# LED_Driver_-_1.net
KiCad netlist of a schematic drawn in Altium Designer
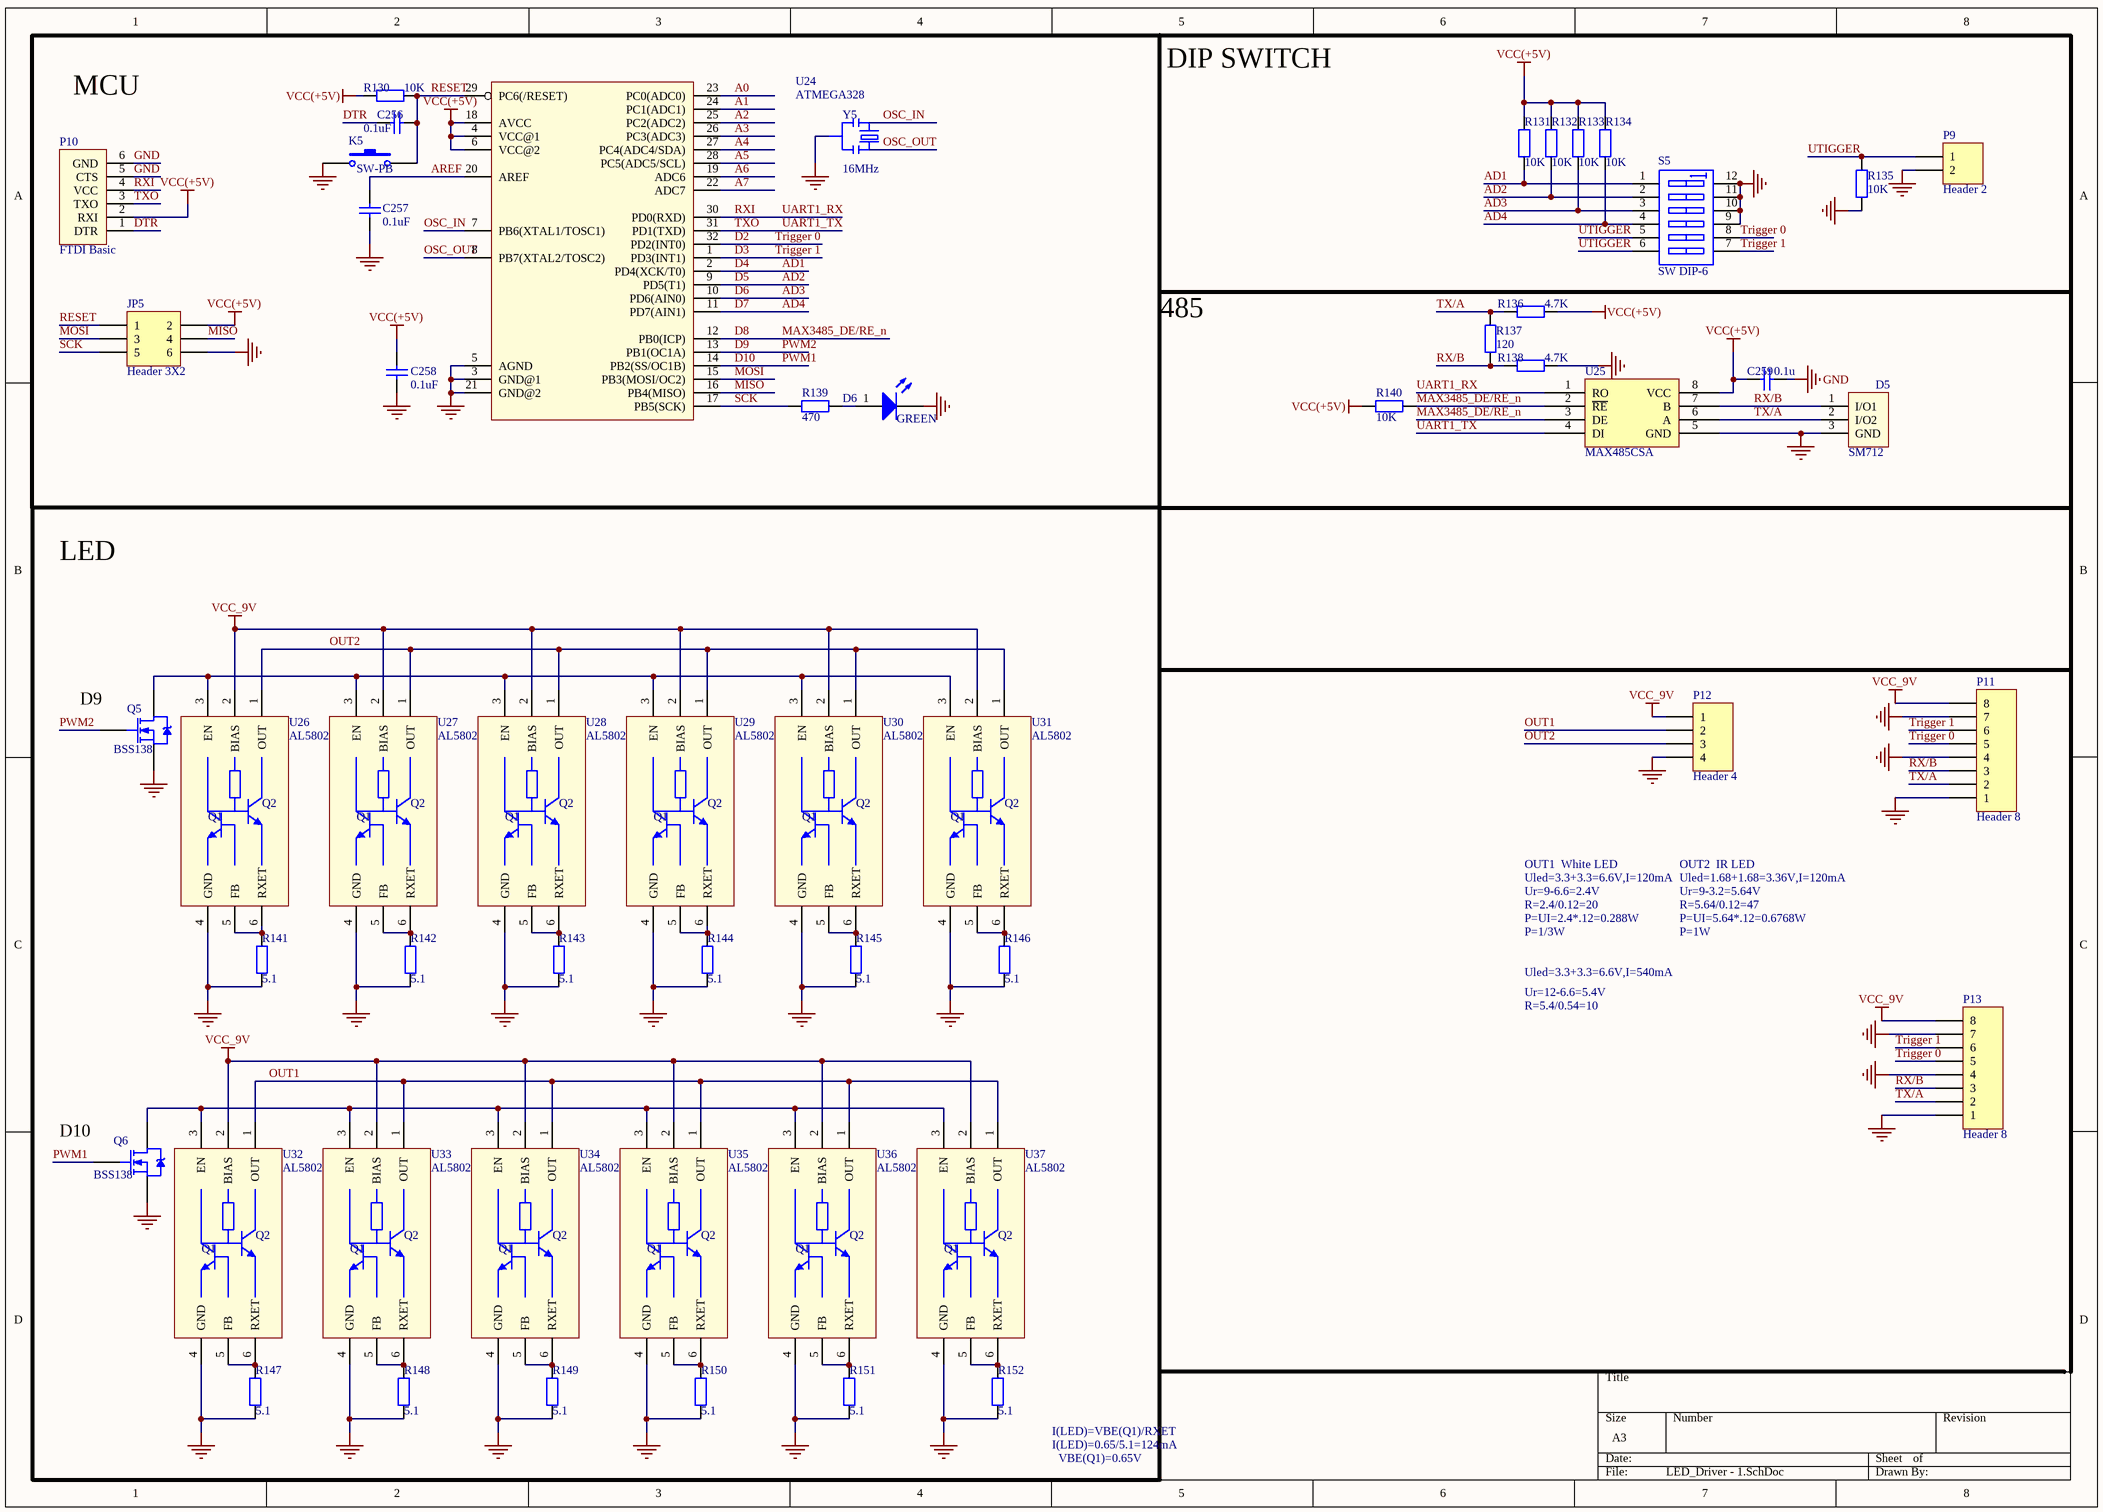
[diagram p0: LED_Driver - 1.SchDoc]

(export (version "E")
  (design (tool "Eeschema 10.0.6"))
  (components
    (comp (ref "C256")
      (value "0.1uF")
      (footprint "C0603")
      (description "Capacitor")
      (fields (field (name "IPARTNUMBER") "C100nF25V10%X7R") (field (name "VOLTAGE") "25V"))
      (libsource (lib "Schlib1") (part "CAP SMT C100nF25V10%X7R"))
    )
    (comp (ref "C257")
      (value "0.1uF")
      (footprint "C0603")
      (description "Capacitor")
      (fields (field (name "IPARTNUMBER") "C100nF25V10%X7R") (field (name "VOLTAGE") "25V"))
      (libsource (lib "Schlib1") (part "CAP SMT C100nF25V10%X7R"))
    )
    (comp (ref "C258")
      (value "0.1uF")
      (footprint "C0603")
      (description "Capacitor")
      (fields (field (name "IPARTNUMBER") "C100nF25V10%X7R") (field (name "VOLTAGE") "25V"))
      (libsource (lib "Schlib1") (part "CAP SMT C100nF25V10%X7R"))
    )
    (comp (ref "C259")
      (value "0.1u")
      (footprint "C0603")
      (description "Capacitor")
      (fields (field (name "PUBLISHER") "Altium Limited"))
      (libsource (lib "Miscellaneous Devices") (part "Cap"))
    )
    (comp (ref "D5")
      (value "SM712")
      (footprint "SOT23-3")
      (libsource (lib "STM32F4_CAM V2.0") (part "SM712"))
    )
    (comp (ref "D6")
      (value "GREEN")
      (footprint "LED0805")
      (description "Typical INFRARED GaAs LED")
      (fields (field (name "PUBLISHER") "Altium Limited"))
      (libsource (lib "DM642") (part "LED0"))
    )
    (comp (ref "JP5")
      (value "Header 3X2")
      (footprint "MHDR1X6")
      (description "Header, 3-Pin, Dual row")
      (fields (field (name "PUBLISHER") "Altium Limited"))
      (libsource (lib "Miscellaneous Connectors") (part "Header 3X2"))
    )
    (comp (ref "K5")
      (value "SW-PB")
      (footprint "157SW")
      (description "Switch")
      (fields (field (name "PUBLISHER") "Altium Limited"))
      (libsource (lib "Miscellaneous Devices") (part "SW-PB"))
    )
    (comp (ref "P9")
      (value "Header 2")
      (footprint "HDR1X2")
      (description "Header, 2-Pin")
      (fields (field (name "PUBLISHER") "Altium Limited"))
      (libsource (lib "Miscellaneous Connectors") (part "Header 2"))
    )
    (comp (ref "P10")
      (value "FTDI Basic")
      (footprint "MHDR1X6")
      (libsource (lib "PCB_Project1") (part "ARDUINO_SERIAL_PROGRAMPTH"))
    )
    (comp (ref "P11")
      (value "Header 8")
      (footprint "SH_1.25MM*8")
      (description "Header, 8-Pin")
      (fields (field (name "PUBLISHER") "Altium Limited"))
      (libsource (lib "Miscellaneous Connectors") (part "Header 8"))
    )
    (comp (ref "P12")
      (value "Header 4")
      (footprint "SMT_1.25MM*4")
      (description "Header, 4-Pin")
      (fields (field (name "PUBLISHER") "Altium Limited"))
      (libsource (lib "Miscellaneous Connectors") (part "Header 4"))
    )
    (comp (ref "P13")
      (value "Header 8")
      (footprint "SH_1.25MM*8")
      (description "Header, 8-Pin")
      (fields (field (name "PUBLISHER") "Altium Limited"))
      (libsource (lib "Miscellaneous Connectors") (part "Header 8"))
    )
    (comp (ref "Q5")
      (value "BSS138")
      (footprint "SOT-23 (Standard)")
      (fields
        (field (name "MANUFACTURER") "Fairchild Semiconductor")
        (field (name "MANUFACTURER PART NUMBER") "BSS123")
      )
      (libsource (lib "Miscellaneous_Devices") (part "NMOS"))
    )
    (comp (ref "Q6")
      (value "BSS138")
      (footprint "SOT-23 (Standard)")
      (fields
        (field (name "MANUFACTURER") "Fairchild Semiconductor")
        (field (name "MANUFACTURER PART NUMBER") "BSS123")
      )
      (libsource (lib "Miscellaneous_Devices") (part "NMOS"))
    )
    (comp (ref "R130")
      (value "10K")
      (footprint "R0603")
      (description "Resistor")
      (libsource (lib "") (part "Res2_2"))
    )
    (comp (ref "R131")
      (value "10K")
      (footprint "R0603")
      (description "Resistor")
      (libsource (lib "") (part "Res2_1"))
    )
    (comp (ref "R132")
      (value "10K")
      (footprint "R0603")
      (description "Resistor")
      (libsource (lib "") (part "Res2_1"))
    )
    (comp (ref "R133")
      (value "10K")
      (footprint "R0603")
      (description "Resistor")
      (libsource (lib "") (part "Res2_1"))
    )
    (comp (ref "R134")
      (value "10K")
      (footprint "R0603")
      (description "Resistor")
      (libsource (lib "") (part "Res2_1"))
    )
    (comp (ref "R135")
      (value "10K")
      (footprint "R0603")
      (description "Resistor")
      (fields (field (name "PUBLISHER") "Altium Limited"))
      (libsource (lib "Miscellaneous Devices") (part "Res2"))
    )
    (comp (ref "R136")
      (value "4.7K")
      (footprint "R0603")
      (description "Resistor")
      (libsource (lib "DM642") (part "Res2"))
    )
    (comp (ref "R137")
      (value "120")
      (footprint "R0603")
      (description "Resistor")
      (libsource (lib "") (part "Res2_1"))
    )
    (comp (ref "R138")
      (value "4.7K")
      (footprint "R0603")
      (description "Resistor")
      (libsource (lib "DM642") (part "Res2"))
    )
    (comp (ref "R139")
      (value "470")
      (footprint "R0603")
      (description "Resistor")
      (libsource (lib "") (part "Res2_2"))
    )
    (comp (ref "R140")
      (value "10K")
      (footprint "R0603")
      (description "Resistor")
      (libsource (lib "DM642") (part "Res2"))
    )
    (comp (ref "R141")
      (value "5.1")
      (footprint "R0603")
      (description "Resistor")
      (libsource (lib "") (part "Res2_1"))
    )
    (comp (ref "R142")
      (value "5.1")
      (footprint "R0603")
      (description "Resistor")
      (libsource (lib "") (part "Res2_1"))
    )
    (comp (ref "R143")
      (value "5.1")
      (footprint "R0603")
      (description "Resistor")
      (libsource (lib "") (part "Res2_1"))
    )
    (comp (ref "R144")
      (value "5.1")
      (footprint "R0603")
      (description "Resistor")
      (libsource (lib "") (part "Res2_1"))
    )
    (comp (ref "R145")
      (value "5.1")
      (footprint "R0603")
      (description "Resistor")
      (libsource (lib "") (part "Res2_1"))
    )
    (comp (ref "R146")
      (value "5.1")
      (footprint "R0603")
      (description "Resistor")
      (libsource (lib "") (part "Res2_1"))
    )
    (comp (ref "R147")
      (value "5.1")
      (footprint "R0603")
      (description "Resistor")
      (libsource (lib "") (part "Res2_1"))
    )
    (comp (ref "R148")
      (value "5.1")
      (footprint "R0603")
      (description "Resistor")
      (libsource (lib "") (part "Res2_1"))
    )
    (comp (ref "R149")
      (value "5.1")
      (footprint "R0603")
      (description "Resistor")
      (libsource (lib "") (part "Res2_1"))
    )
    (comp (ref "R150")
      (value "5.1")
      (footprint "R0603")
      (description "Resistor")
      (libsource (lib "") (part "Res2_1"))
    )
    (comp (ref "R151")
      (value "5.1")
      (footprint "R0603")
      (description "Resistor")
      (libsource (lib "") (part "Res2_1"))
    )
    (comp (ref "R152")
      (value "5.1")
      (footprint "R0603")
      (description "Resistor")
      (libsource (lib "") (part "Res2_1"))
    )
    (comp (ref "S5")
      (value "SW DIP-6")
      (footprint "DIP_SW_6WAY_SMD")
      (description "DIP Switch, 6 Position, SPST")
      (fields (field (name "PUBLISHER") "Altium Limited"))
      (libsource (lib "Miscellaneous Devices") (part "SW DIP-6"))
    )
    (comp (ref "U24")
      (value "ATMEGA328")
      (footprint "TQFP32-08")
      (libsource (lib "PCB_Project1") (part "ATMEGA168"))
    )
    (comp (ref "U25")
      (value "MAX485CSA")
      (footprint "SOIC-8")
      (libsource (lib "STM32F4_CAM V1.2") (part "MAX3485CSA"))
    )
    (comp (ref "U26") (value "AL5802") (footprint "SOT26") (libsource (lib "LED") (part "AL5802")))
    (comp (ref "U27") (value "AL5802") (footprint "SOT26") (libsource (lib "LED") (part "AL5802")))
    (comp (ref "U28") (value "AL5802") (footprint "SOT26") (libsource (lib "LED") (part "AL5802")))
    (comp (ref "U29") (value "AL5802") (footprint "SOT26") (libsource (lib "LED") (part "AL5802")))
    (comp (ref "U30") (value "AL5802") (footprint "SOT26") (libsource (lib "LED") (part "AL5802")))
    (comp (ref "U31") (value "AL5802") (footprint "SOT26") (libsource (lib "LED") (part "AL5802")))
    (comp (ref "U32") (value "AL5802") (footprint "SOT26") (libsource (lib "LED") (part "AL5802")))
    (comp (ref "U33") (value "AL5802") (footprint "SOT26") (libsource (lib "LED") (part "AL5802")))
    (comp (ref "U34") (value "AL5802") (footprint "SOT26") (libsource (lib "LED") (part "AL5802")))
    (comp (ref "U35") (value "AL5802") (footprint "SOT26") (libsource (lib "LED") (part "AL5802")))
    (comp (ref "U36") (value "AL5802") (footprint "SOT26") (libsource (lib "LED") (part "AL5802")))
    (comp (ref "U37") (value "AL5802") (footprint "SOT26") (libsource (lib "LED") (part "AL5802")))
    (comp (ref "Y5")
      (value "16MHz")
      (footprint "RESONATOR-SMD")
      (libsource (lib "SparkFun") (part "RESONATORSMD"))
    )
  )
  (nets
    (net (code "1") (name "/A0") (class "Default")
      (node (ref "U24") (pin "23") (pinfunction "PC0(ADC0)_23") (pintype "passive"))
    )
    (net (code "2") (name "/A1") (class "Default")
      (node (ref "U24") (pin "24") (pinfunction "PC1(ADC1)_24") (pintype "passive"))
    )
    (net (code "3") (name "/A2") (class "Default")
      (node (ref "U24") (pin "25") (pinfunction "PC2(ADC2)_25") (pintype "passive"))
    )
    (net (code "4") (name "/A3") (class "Default")
      (node (ref "U24") (pin "26") (pinfunction "PC3(ADC3)_26") (pintype "passive"))
    )
    (net (code "5") (name "/A4") (class "Default")
      (node (ref "U24") (pin "27") (pinfunction "PC4(ADC4/SDA)_27") (pintype "passive"))
    )
    (net (code "6") (name "/A5") (class "Default")
      (node (ref "U24") (pin "28") (pinfunction "PC5(ADC5/SCL)_28") (pintype "passive"))
    )
    (net (code "7") (name "/A6") (class "Default")
      (node (ref "U24") (pin "19") (pinfunction "ADC6_19") (pintype "passive"))
    )
    (net (code "8") (name "/A7") (class "Default")
      (node (ref "U24") (pin "22") (pinfunction "ADC7_22") (pintype "passive"))
    )
    (net (code "9") (name "/AD1") (class "Default")
      (node (ref "R131") (pin "2") (pinfunction "2_2") (pintype "passive"))
      (node (ref "S5") (pin "1") (pinfunction "A1_1") (pintype "passive"))
      (node (ref "U24") (pin "2") (pinfunction "PD4(XCK/T0)_2") (pintype "passive"))
    )
    (net (code "10") (name "/AD2") (class "Default")
      (node (ref "R132") (pin "2") (pinfunction "2_2") (pintype "passive"))
      (node (ref "S5") (pin "2") (pinfunction "A2_2") (pintype "passive"))
      (node (ref "U24") (pin "9") (pinfunction "PD5(T1)_9") (pintype "passive"))
    )
    (net (code "11") (name "/AD3") (class "Default")
      (node (ref "R133") (pin "2") (pinfunction "2_2") (pintype "passive"))
      (node (ref "S5") (pin "3") (pinfunction "A3_3") (pintype "passive"))
      (node (ref "U24") (pin "10") (pinfunction "PD6(AIN0)_10") (pintype "passive"))
    )
    (net (code "12") (name "/AD4") (class "Default")
      (node (ref "R134") (pin "2") (pinfunction "2_2") (pintype "passive"))
      (node (ref "S5") (pin "4") (pinfunction "A4_4") (pintype "passive"))
      (node (ref "U24") (pin "11") (pinfunction "PD7(AIN1)_11") (pintype "passive"))
    )
    (net (code "13") (name "/AREF") (class "Default")
      (node (ref "C257") (pin "2") (pinfunction "2_2") (pintype "passive"))
      (node (ref "U24") (pin "20") (pinfunction "AREF_20") (pintype "passive"))
    )
    (net (code "14") (name "/D2") (class "Default")
      (node (ref "P11") (pin "5") (pinfunction "5_5") (pintype "passive"))
      (node (ref "P13") (pin "5") (pinfunction "5_5") (pintype "passive"))
      (node (ref "S5") (pin "8") (pinfunction "B5_8") (pintype "passive"))
      (node (ref "U24") (pin "32") (pinfunction "PD2(INT0)_32") (pintype "passive"))
    )
    (net (code "15") (name "/D3") (class "Default")
      (node (ref "P11") (pin "6") (pinfunction "6_6") (pintype "passive"))
      (node (ref "P13") (pin "6") (pinfunction "6_6") (pintype "passive"))
      (node (ref "S5") (pin "7") (pinfunction "B6_7") (pintype "passive"))
      (node (ref "U24") (pin "1") (pinfunction "PD3(INT1)_1") (pintype "passive"))
    )
    (net (code "16") (name "/D8") (class "Default")
      (node (ref "R140") (pin "1") (pinfunction "1_1") (pintype "passive"))
      (node (ref "U24") (pin "12") (pinfunction "PB0(ICP)_12") (pintype "passive"))
      (node (ref "U25") (pin "2") (pinfunction "~{RE}_2") (pintype "passive"))
      (node (ref "U25") (pin "3") (pinfunction "DE_3") (pintype "passive"))
    )
    (net (code "17") (name "/D9") (class "Default")
      (node (ref "Q5") (pin "G") (pinfunction "G_G") (pintype "passive"))
      (node (ref "U24") (pin "13") (pinfunction "PB1(OC1A)_13") (pintype "passive"))
    )
    (net (code "18") (name "/D10") (class "Default")
      (node (ref "Q6") (pin "G") (pinfunction "G_G") (pintype "passive"))
      (node (ref "U24") (pin "14") (pinfunction "PB2(SS/OC1B)_14") (pintype "passive"))
    )
    (net (code "19") (name "/DTR") (class "Default")
      (node (ref "C256") (pin "1") (pinfunction "1_1") (pintype "passive"))
      (node (ref "P10") (pin "1") (pinfunction "DTR_1") (pintype "passive"))
    )
    (net (code "20") (name "/MISO") (class "Default")
      (node (ref "JP5") (pin "4") (pinfunction "4_4") (pintype "passive"))
      (node (ref "U24") (pin "16") (pinfunction "PB4(MISO)_16") (pintype "passive"))
    )
    (net (code "21") (name "/MOSI") (class "Default")
      (node (ref "JP5") (pin "3") (pinfunction "3_3") (pintype "passive"))
      (node (ref "U24") (pin "15") (pinfunction "PB3(MOSI/OC2)_15") (pintype "passive"))
    )
    (net (code "22") (name "/OSC_IN") (class "Default")
      (node (ref "U24") (pin "7") (pinfunction "PB6(XTAL1/TOSC1)_7") (pintype "passive"))
      (node (ref "Y5") (pin "3") (pinfunction "3_3") (pintype "passive"))
    )
    (net (code "23") (name "/OSC_OUT") (class "Default")
      (node (ref "U24") (pin "8") (pinfunction "PB7(XTAL2/TOSC2)_8") (pintype "passive"))
      (node (ref "Y5") (pin "1") (pinfunction "1_1") (pintype "passive"))
    )
    (net (code "24") (name "/OUT1") (class "Default")
      (node (ref "P12") (pin "2") (pinfunction "2_2") (pintype "passive"))
      (node (ref "U32") (pin "1") (pinfunction "OUT_1") (pintype "passive"))
      (node (ref "U33") (pin "1") (pinfunction "OUT_1") (pintype "passive"))
      (node (ref "U34") (pin "1") (pinfunction "OUT_1") (pintype "passive"))
      (node (ref "U35") (pin "1") (pinfunction "OUT_1") (pintype "passive"))
      (node (ref "U36") (pin "1") (pinfunction "OUT_1") (pintype "passive"))
      (node (ref "U37") (pin "1") (pinfunction "OUT_1") (pintype "passive"))
    )
    (net (code "25") (name "/OUT2") (class "Default")
      (node (ref "P12") (pin "3") (pinfunction "3_3") (pintype "passive"))
      (node (ref "U26") (pin "1") (pinfunction "OUT_1") (pintype "passive"))
      (node (ref "U27") (pin "1") (pinfunction "OUT_1") (pintype "passive"))
      (node (ref "U28") (pin "1") (pinfunction "OUT_1") (pintype "passive"))
      (node (ref "U29") (pin "1") (pinfunction "OUT_1") (pintype "passive"))
      (node (ref "U30") (pin "1") (pinfunction "OUT_1") (pintype "passive"))
      (node (ref "U31") (pin "1") (pinfunction "OUT_1") (pintype "passive"))
    )
    (net (code "26") (name "/RESET") (class "Default")
      (node (ref "C256") (pin "2") (pinfunction "2_2") (pintype "passive"))
      (node (ref "JP5") (pin "1") (pinfunction "1_1") (pintype "passive"))
      (node (ref "K5") (pin "2") (pinfunction "2_2") (pintype "passive"))
      (node (ref "R130") (pin "2") (pinfunction "2_2") (pintype "passive"))
      (node (ref "U24") (pin "29") (pinfunction "PC6(/RESET)_29") (pintype "passive"))
    )
    (net (code "27") (name "/RXI") (class "Default")
      (node (ref "P10") (pin "4") (pinfunction "VCC_4") (pintype "passive"))
      (node (ref "U24") (pin "30") (pinfunction "PD0(RXD)_30") (pintype "passive"))
      (node (ref "U25") (pin "1") (pinfunction "RO_1") (pintype "passive"))
    )
    (net (code "28") (name "/RX{slash}B") (class "Default")
      (node (ref "D5") (pin "1") (pinfunction "I/O1_1") (pintype "passive"))
      (node (ref "P11") (pin "3") (pinfunction "3_3") (pintype "passive"))
      (node (ref "P13") (pin "3") (pinfunction "3_3") (pintype "passive"))
      (node (ref "R137") (pin "2") (pinfunction "2_2") (pintype "passive"))
      (node (ref "R138") (pin "2") (pinfunction "2_2") (pintype "passive"))
      (node (ref "U25") (pin "7") (pinfunction "B_7") (pintype "passive"))
    )
    (net (code "29") (name "/SCK") (class "Default")
      (node (ref "JP5") (pin "5") (pinfunction "5_5") (pintype "passive"))
      (node (ref "R139") (pin "1") (pinfunction "1_1") (pintype "passive"))
      (node (ref "U24") (pin "17") (pinfunction "PB5(SCK)_17") (pintype "passive"))
    )
    (net (code "30") (name "/TXO") (class "Default")
      (node (ref "P10") (pin "3") (pinfunction "TXO_3") (pintype "passive"))
      (node (ref "U24") (pin "31") (pinfunction "PD1(TXD)_31") (pintype "passive"))
      (node (ref "U25") (pin "4") (pinfunction "DI_4") (pintype "passive"))
    )
    (net (code "31") (name "/TX{slash}A") (class "Default")
      (node (ref "D5") (pin "2") (pinfunction "I/O2_2") (pintype "passive"))
      (node (ref "P11") (pin "2") (pinfunction "2_2") (pintype "passive"))
      (node (ref "P13") (pin "2") (pinfunction "2_2") (pintype "passive"))
      (node (ref "R136") (pin "2") (pinfunction "2_2") (pintype "passive"))
      (node (ref "R137") (pin "1") (pinfunction "1_1") (pintype "passive"))
      (node (ref "U25") (pin "6") (pinfunction "A_6") (pintype "passive"))
    )
    (net (code "32") (name "/UTIGGER") (class "Default")
      (node (ref "P9") (pin "1") (pinfunction "1_1") (pintype "passive"))
      (node (ref "R135") (pin "2") (pinfunction "2_2") (pintype "passive"))
      (node (ref "S5") (pin "5") (pinfunction "A5_5") (pintype "passive"))
      (node (ref "S5") (pin "6") (pinfunction "A6_6") (pintype "passive"))
    )
    (net (code "33") (name "GND") (class "Default")
      (node (ref "C257") (pin "1") (pinfunction "1_1") (pintype "passive"))
      (node (ref "C258") (pin "2") (pinfunction "2_2") (pintype "passive"))
      (node (ref "C259") (pin "1") (pinfunction "1_1") (pintype "passive"))
      (node (ref "D5") (pin "3") (pinfunction "GND_3") (pintype "passive"))
      (node (ref "D6") (pin "2") (pinfunction "K_2") (pintype "passive"))
      (node (ref "JP5") (pin "6") (pinfunction "6_6") (pintype "passive"))
      (node (ref "K5") (pin "1") (pinfunction "1_1") (pintype "passive"))
      (node (ref "P10") (pin "5") (pinfunction "CTS_5") (pintype "passive"))
      (node (ref "P10") (pin "6") (pinfunction "GND_6") (pintype "passive"))
      (node (ref "P11") (pin "1") (pinfunction "1_1") (pintype "passive"))
      (node (ref "P11") (pin "4") (pinfunction "4_4") (pintype "passive"))
      (node (ref "P11") (pin "7") (pinfunction "7_7") (pintype "passive"))
      (node (ref "P12") (pin "4") (pinfunction "4_4") (pintype "passive"))
      (node (ref "P13") (pin "1") (pinfunction "1_1") (pintype "passive"))
      (node (ref "P13") (pin "4") (pinfunction "4_4") (pintype "passive"))
      (node (ref "P13") (pin "7") (pinfunction "7_7") (pintype "passive"))
      (node (ref "P9") (pin "2") (pinfunction "2_2") (pintype "passive"))
      (node (ref "Q5") (pin "S") (pinfunction "S_S") (pintype "passive"))
      (node (ref "Q6") (pin "S") (pinfunction "S_S") (pintype "passive"))
      (node (ref "R135") (pin "1") (pinfunction "1_1") (pintype "passive"))
      (node (ref "R138") (pin "1") (pinfunction "1_1") (pintype "passive"))
      (node (ref "R141") (pin "2") (pinfunction "2_2") (pintype "passive"))
      (node (ref "R142") (pin "2") (pinfunction "2_2") (pintype "passive"))
      (node (ref "R143") (pin "2") (pinfunction "2_2") (pintype "passive"))
      (node (ref "R144") (pin "2") (pinfunction "2_2") (pintype "passive"))
      (node (ref "R145") (pin "2") (pinfunction "2_2") (pintype "passive"))
      (node (ref "R146") (pin "2") (pinfunction "2_2") (pintype "passive"))
      (node (ref "R147") (pin "2") (pinfunction "2_2") (pintype "passive"))
      (node (ref "R148") (pin "2") (pinfunction "2_2") (pintype "passive"))
      (node (ref "R149") (pin "2") (pinfunction "2_2") (pintype "passive"))
      (node (ref "R150") (pin "2") (pinfunction "2_2") (pintype "passive"))
      (node (ref "R151") (pin "2") (pinfunction "2_2") (pintype "passive"))
      (node (ref "R152") (pin "2") (pinfunction "2_2") (pintype "passive"))
      (node (ref "S5") (pin "10") (pinfunction "B3_10") (pintype "passive"))
      (node (ref "S5") (pin "11") (pinfunction "B2_11") (pintype "passive"))
      (node (ref "S5") (pin "12") (pinfunction "B1_12") (pintype "passive"))
      (node (ref "S5") (pin "9") (pinfunction "B4_9") (pintype "passive"))
      (node (ref "U24") (pin "21") (pinfunction "GND@2_21") (pintype "passive"))
      (node (ref "U24") (pin "3") (pinfunction "GND@1_3") (pintype "passive"))
      (node (ref "U24") (pin "5") (pinfunction "AGND_5") (pintype "passive"))
      (node (ref "U25") (pin "5") (pinfunction "GND_5") (pintype "passive"))
      (node (ref "U26") (pin "4") (pinfunction "GND_4") (pintype "passive"))
      (node (ref "U27") (pin "4") (pinfunction "GND_4") (pintype "passive"))
      (node (ref "U28") (pin "4") (pinfunction "GND_4") (pintype "passive"))
      (node (ref "U29") (pin "4") (pinfunction "GND_4") (pintype "passive"))
      (node (ref "U30") (pin "4") (pinfunction "GND_4") (pintype "passive"))
      (node (ref "U31") (pin "4") (pinfunction "GND_4") (pintype "passive"))
      (node (ref "U32") (pin "4") (pinfunction "GND_4") (pintype "passive"))
      (node (ref "U33") (pin "4") (pinfunction "GND_4") (pintype "passive"))
      (node (ref "U34") (pin "4") (pinfunction "GND_4") (pintype "passive"))
      (node (ref "U35") (pin "4") (pinfunction "GND_4") (pintype "passive"))
      (node (ref "U36") (pin "4") (pinfunction "GND_4") (pintype "passive"))
      (node (ref "U37") (pin "4") (pinfunction "GND_4") (pintype "passive"))
      (node (ref "Y5") (pin "2") (pinfunction "2_2") (pintype "passive"))
    )
    (net (code "34") (name "Net-(D6-A)") (class "Default")
      (node (ref "D6") (pin "1") (pinfunction "A_1") (pintype "passive"))
      (node (ref "R139") (pin "2") (pinfunction "2_2") (pintype "passive"))
    )
    (net (code "35") (name "Net-(U26-EN)") (class "Default")
      (node (ref "Q5") (pin "D") (pinfunction "D_D") (pintype "passive"))
      (node (ref "U26") (pin "3") (pinfunction "EN_3") (pintype "passive"))
      (node (ref "U27") (pin "3") (pinfunction "EN_3") (pintype "passive"))
      (node (ref "U28") (pin "3") (pinfunction "EN_3") (pintype "passive"))
      (node (ref "U29") (pin "3") (pinfunction "EN_3") (pintype "passive"))
      (node (ref "U30") (pin "3") (pinfunction "EN_3") (pintype "passive"))
      (node (ref "U31") (pin "3") (pinfunction "EN_3") (pintype "passive"))
    )
    (net (code "36") (name "Net-(U26-FB)") (class "Default")
      (node (ref "R141") (pin "1") (pinfunction "1_1") (pintype "passive"))
      (node (ref "U26") (pin "5") (pinfunction "FB_5") (pintype "passive"))
      (node (ref "U26") (pin "6") (pinfunction "RXET_6") (pintype "passive"))
    )
    (net (code "37") (name "Net-(U27-FB)") (class "Default")
      (node (ref "R142") (pin "1") (pinfunction "1_1") (pintype "passive"))
      (node (ref "U27") (pin "5") (pinfunction "FB_5") (pintype "passive"))
      (node (ref "U27") (pin "6") (pinfunction "RXET_6") (pintype "passive"))
    )
    (net (code "38") (name "Net-(U28-FB)") (class "Default")
      (node (ref "R143") (pin "1") (pinfunction "1_1") (pintype "passive"))
      (node (ref "U28") (pin "5") (pinfunction "FB_5") (pintype "passive"))
      (node (ref "U28") (pin "6") (pinfunction "RXET_6") (pintype "passive"))
    )
    (net (code "39") (name "Net-(U29-FB)") (class "Default")
      (node (ref "R144") (pin "1") (pinfunction "1_1") (pintype "passive"))
      (node (ref "U29") (pin "5") (pinfunction "FB_5") (pintype "passive"))
      (node (ref "U29") (pin "6") (pinfunction "RXET_6") (pintype "passive"))
    )
    (net (code "40") (name "Net-(U30-FB)") (class "Default")
      (node (ref "R145") (pin "1") (pinfunction "1_1") (pintype "passive"))
      (node (ref "U30") (pin "5") (pinfunction "FB_5") (pintype "passive"))
      (node (ref "U30") (pin "6") (pinfunction "RXET_6") (pintype "passive"))
    )
    (net (code "41") (name "Net-(U31-FB)") (class "Default")
      (node (ref "R146") (pin "1") (pinfunction "1_1") (pintype "passive"))
      (node (ref "U31") (pin "5") (pinfunction "FB_5") (pintype "passive"))
      (node (ref "U31") (pin "6") (pinfunction "RXET_6") (pintype "passive"))
    )
    (net (code "42") (name "Net-(U32-EN)") (class "Default")
      (node (ref "Q6") (pin "D") (pinfunction "D_D") (pintype "passive"))
      (node (ref "U32") (pin "3") (pinfunction "EN_3") (pintype "passive"))
      (node (ref "U33") (pin "3") (pinfunction "EN_3") (pintype "passive"))
      (node (ref "U34") (pin "3") (pinfunction "EN_3") (pintype "passive"))
      (node (ref "U35") (pin "3") (pinfunction "EN_3") (pintype "passive"))
      (node (ref "U36") (pin "3") (pinfunction "EN_3") (pintype "passive"))
      (node (ref "U37") (pin "3") (pinfunction "EN_3") (pintype "passive"))
    )
    (net (code "43") (name "Net-(U32-FB)") (class "Default")
      (node (ref "R147") (pin "1") (pinfunction "1_1") (pintype "passive"))
      (node (ref "U32") (pin "5") (pinfunction "FB_5") (pintype "passive"))
      (node (ref "U32") (pin "6") (pinfunction "RXET_6") (pintype "passive"))
    )
    (net (code "44") (name "Net-(U33-FB)") (class "Default")
      (node (ref "R148") (pin "1") (pinfunction "1_1") (pintype "passive"))
      (node (ref "U33") (pin "5") (pinfunction "FB_5") (pintype "passive"))
      (node (ref "U33") (pin "6") (pinfunction "RXET_6") (pintype "passive"))
    )
    (net (code "45") (name "Net-(U34-FB)") (class "Default")
      (node (ref "R149") (pin "1") (pinfunction "1_1") (pintype "passive"))
      (node (ref "U34") (pin "5") (pinfunction "FB_5") (pintype "passive"))
      (node (ref "U34") (pin "6") (pinfunction "RXET_6") (pintype "passive"))
    )
    (net (code "46") (name "Net-(U35-FB)") (class "Default")
      (node (ref "R150") (pin "1") (pinfunction "1_1") (pintype "passive"))
      (node (ref "U35") (pin "5") (pinfunction "FB_5") (pintype "passive"))
      (node (ref "U35") (pin "6") (pinfunction "RXET_6") (pintype "passive"))
    )
    (net (code "47") (name "Net-(U36-FB)") (class "Default")
      (node (ref "R151") (pin "1") (pinfunction "1_1") (pintype "passive"))
      (node (ref "U36") (pin "5") (pinfunction "FB_5") (pintype "passive"))
      (node (ref "U36") (pin "6") (pinfunction "RXET_6") (pintype "passive"))
    )
    (net (code "48") (name "Net-(U37-FB)") (class "Default")
      (node (ref "R152") (pin "1") (pinfunction "1_1") (pintype "passive"))
      (node (ref "U37") (pin "5") (pinfunction "FB_5") (pintype "passive"))
      (node (ref "U37") (pin "6") (pinfunction "RXET_6") (pintype "passive"))
    )
    (net (code "49") (name "VCC(+5V)") (class "Default")
      (node (ref "C258") (pin "1") (pinfunction "1_1") (pintype "passive"))
      (node (ref "C259") (pin "2") (pinfunction "2_2") (pintype "passive"))
      (node (ref "JP5") (pin "2") (pinfunction "2_2") (pintype "passive"))
      (node (ref "P10") (pin "2") (pinfunction "RXI_2") (pintype "passive"))
      (node (ref "R130") (pin "1") (pinfunction "1_1") (pintype "passive"))
      (node (ref "R131") (pin "1") (pinfunction "1_1") (pintype "passive"))
      (node (ref "R132") (pin "1") (pinfunction "1_1") (pintype "passive"))
      (node (ref "R133") (pin "1") (pinfunction "1_1") (pintype "passive"))
      (node (ref "R134") (pin "1") (pinfunction "1_1") (pintype "passive"))
      (node (ref "R136") (pin "1") (pinfunction "1_1") (pintype "passive"))
      (node (ref "R140") (pin "2") (pinfunction "2_2") (pintype "passive"))
      (node (ref "U24") (pin "18") (pinfunction "AVCC_18") (pintype "passive"))
      (node (ref "U24") (pin "4") (pinfunction "VCC@1_4") (pintype "passive"))
      (node (ref "U24") (pin "6") (pinfunction "VCC@2_6") (pintype "passive"))
      (node (ref "U25") (pin "8") (pinfunction "VCC_8") (pintype "passive"))
    )
    (net (code "50") (name "VCC_9V") (class "Default")
      (node (ref "P11") (pin "8") (pinfunction "8_8") (pintype "passive"))
      (node (ref "P12") (pin "1") (pinfunction "1_1") (pintype "passive"))
      (node (ref "P13") (pin "8") (pinfunction "8_8") (pintype "passive"))
      (node (ref "U26") (pin "2") (pinfunction "BIAS_2") (pintype "passive"))
      (node (ref "U27") (pin "2") (pinfunction "BIAS_2") (pintype "passive"))
      (node (ref "U28") (pin "2") (pinfunction "BIAS_2") (pintype "passive"))
      (node (ref "U29") (pin "2") (pinfunction "BIAS_2") (pintype "passive"))
      (node (ref "U30") (pin "2") (pinfunction "BIAS_2") (pintype "passive"))
      (node (ref "U31") (pin "2") (pinfunction "BIAS_2") (pintype "passive"))
      (node (ref "U32") (pin "2") (pinfunction "BIAS_2") (pintype "passive"))
      (node (ref "U33") (pin "2") (pinfunction "BIAS_2") (pintype "passive"))
      (node (ref "U34") (pin "2") (pinfunction "BIAS_2") (pintype "passive"))
      (node (ref "U35") (pin "2") (pinfunction "BIAS_2") (pintype "passive"))
      (node (ref "U36") (pin "2") (pinfunction "BIAS_2") (pintype "passive"))
      (node (ref "U37") (pin "2") (pinfunction "BIAS_2") (pintype "passive"))
    )
  )
)
